# F103___2025-11-19.net
KiCad netlist of a schematic drawn in EasyEDA Pro
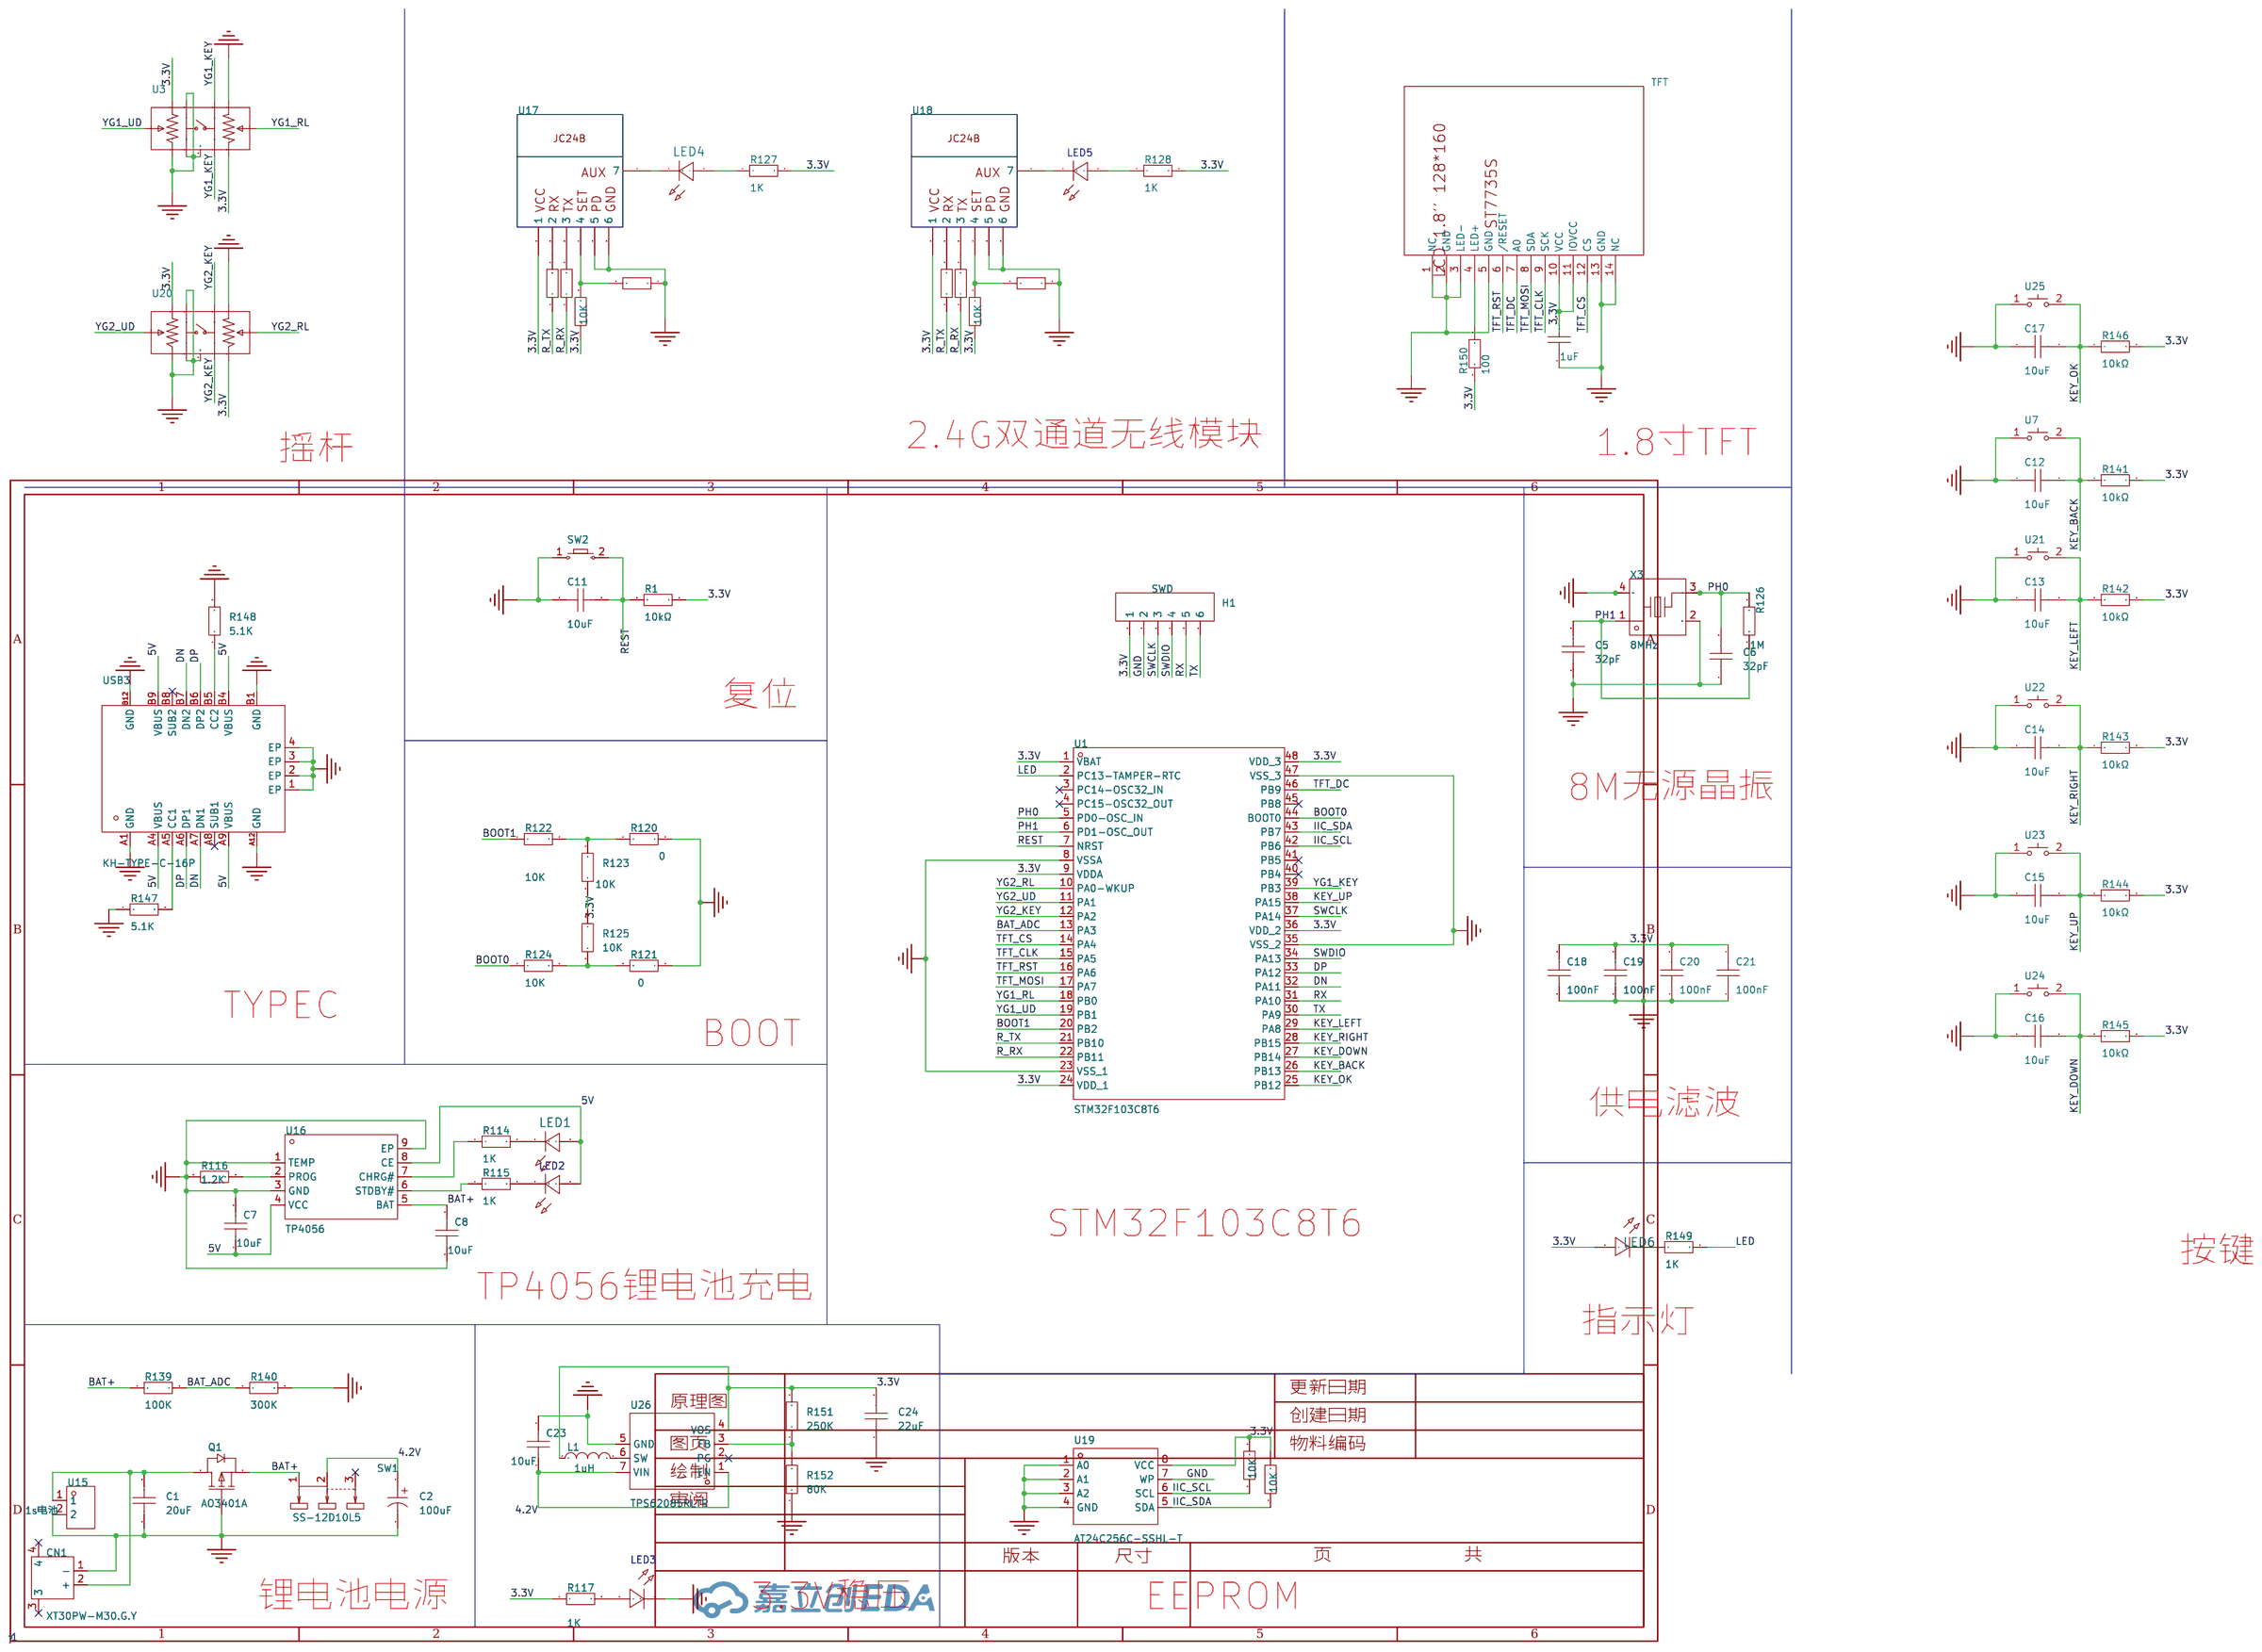
[diagram p0: schematic sheet]

(export (version "E")
  (design (tool "Eeschema 10.0.6"))
  (components
    (comp (ref "C1")
      (value "20uF")
      (footprint "easyedapro:C0805")
      (libsource (lib "easyedapro") (part "CapAcitance"))
    )
    (comp (ref "C2")
      (value "100uF")
      (footprint "easyedapro:CAP-SMD_BD6.3-L6.6-W6.6-LS7.4-FD")
      (description "容值:100uF;精度:±20%;额定电压:35V;纹波电流:87mA@120kHz;等效串联电阻:-;")
      (fields
        (field (name "Manufacturer Part") "RVT100UF35V67RV0034")
        (field (name "Manufacturer") "KNSCHA(科尼盛)")
      )
      (libsource (lib "easyedapro") (part "RVT100UF35V67RV0034"))
    )
    (comp (ref "C5")
      (value "32pF")
      (footprint "easyedapro:C0805")
      (libsource (lib "easyedapro") (part "CapAcitance"))
    )
    (comp (ref "C6")
      (value "32pF")
      (footprint "easyedapro:C0805")
      (libsource (lib "easyedapro") (part "CapAcitance"))
    )
    (comp (ref "C7")
      (value "10uF")
      (footprint "easyedapro:C0805")
      (libsource (lib "easyedapro") (part "CapAcitance"))
    )
    (comp (ref "C8")
      (value "10uF")
      (footprint "easyedapro:C0805")
      (libsource (lib "easyedapro") (part "CapAcitance"))
    )
    (comp (ref "C11")
      (value "10uF")
      (footprint "easyedapro:C0805")
      (libsource (lib "easyedapro") (part "CapAcitance"))
    )
    (comp (ref "C12")
      (value "10uF")
      (footprint "easyedapro:C0805")
      (libsource (lib "easyedapro") (part "CapAcitance"))
    )
    (comp (ref "C13")
      (value "10uF")
      (footprint "easyedapro:C0805")
      (libsource (lib "easyedapro") (part "CapAcitance"))
    )
    (comp (ref "C14")
      (value "10uF")
      (footprint "easyedapro:C0805")
      (libsource (lib "easyedapro") (part "CapAcitance"))
    )
    (comp (ref "C15")
      (value "10uF")
      (footprint "easyedapro:C0805")
      (libsource (lib "easyedapro") (part "CapAcitance"))
    )
    (comp (ref "C16")
      (value "10uF")
      (footprint "easyedapro:C0805")
      (libsource (lib "easyedapro") (part "CapAcitance"))
    )
    (comp (ref "C17")
      (value "10uF")
      (footprint "easyedapro:C0805")
      (libsource (lib "easyedapro") (part "CapAcitance"))
    )
    (comp (ref "C18")
      (value "100nF")
      (footprint "easyedapro:C0805")
      (libsource (lib "easyedapro") (part "CapAcitance"))
    )
    (comp (ref "C19")
      (value "100nF")
      (footprint "easyedapro:C0805")
      (libsource (lib "easyedapro") (part "CapAcitance"))
    )
    (comp (ref "C20")
      (value "100nF")
      (footprint "easyedapro:C0805")
      (libsource (lib "easyedapro") (part "CapAcitance"))
    )
    (comp (ref "C21")
      (value "100nF")
      (footprint "easyedapro:C0805")
      (libsource (lib "easyedapro") (part "CapAcitance"))
    )
    (comp (ref "C22")
      (value "1uF")
      (footprint "easyedapro:C0805")
      (libsource (lib "easyedapro") (part "CapAcitance"))
    )
    (comp (ref "C23")
      (value "10uF")
      (footprint "easyedapro:C0805")
      (libsource (lib "easyedapro") (part "CapAcitance"))
    )
    (comp (ref "C24")
      (value "22uF")
      (footprint "easyedapro:C0805")
      (libsource (lib "easyedapro") (part "CapAcitance"))
    )
    (comp (ref "CN1")
      (value "XT30PW-M30.G.Y")
      (footprint "easyedapro:CONN-TH_XT30PW-M")
      (description "类别:-;类型1:-;")
      (fields (field (name "Manufacturer") "AMASS(艾迈斯)"))
      (libsource (lib "easyedapro") (part "XT30PW-M"))
    )
    (comp (ref "H1")
      (value "SWD")
      (footprint "easyedapro:HDR-TH_6P-P2.54-V-M-1")
      (libsource (lib "easyedapro") (part "Header-Male-2.54_1x6"))
    )
    (comp (ref "L1")
      (value "1uH")
      (footprint "easyedapro:IND-SMD_L5.4-W5.2_FXL0530")
      (description "电感值:1uH;精度:±20%;额定电流:8.5A;饱和电流(Isat):11A;类型:一体成型电感;")
      (fields (field (name "Manufacturer Part") "FXL0530-1R0-M") (field (name "Manufacturer") "cjiang(长江微电)"))
      (libsource (lib "easyedapro") (part "FXL0530-1R0-M"))
    )
    (comp (ref "LCD2")
      (value "TFT")
      (footprint "easyedapro:1.8寸TFT")
      (description "1.8寸，ST7735S")
      (libsource (lib "easyedapro") (part "LCD-1.8&apos;&apos;-128*160-ST7735S"))
    )
    (comp (ref "LED1")
      (value "~")
      (footprint "easyedapro:LED_0805")
      (libsource (lib "easyedapro") (part "LED_R"))
    )
    (comp (ref "LED2")
      (value "~")
      (footprint "easyedapro:LED_0805")
      (libsource (lib "easyedapro") (part "LED_B"))
    )
    (comp (ref "LED3")
      (value "~")
      (footprint "easyedapro:LED_0805")
      (libsource (lib "easyedapro") (part "LED_G"))
    )
    (comp (ref "LED4")
      (value "~")
      (footprint "easyedapro:LED_0805")
      (libsource (lib "easyedapro") (part "LED_R"))
    )
    (comp (ref "LED5")
      (value "~")
      (footprint "easyedapro:LED_0805")
      (libsource (lib "easyedapro") (part "LED_B"))
    )
    (comp (ref "LED6")
      (value "~")
      (footprint "easyedapro:LED_0805")
      (libsource (lib "easyedapro") (part "LED_R"))
    )
    (comp (ref "Q1")
      (value "AO3401A")
      (footprint "easyedapro:SOT-23_L2.9-W1.3-P1.90-LS2.4-BR")
      (fields (field (name "Manufacturer") "AOS"))
      (libsource (lib "easyedapro") (part "AO3401A"))
    )
    (comp (ref "R1")
      (value "10kΩ")
      (footprint "easyedapro:R0805")
      (description "电阻类型:厚膜电阻;阻值:4.7kΩ;精度:±1%;功率:125mW;最大工作电压:150V;温度系数:±100ppm/°C;")
      (fields
        (field (name "Manufacturer Part") "0805W8F4701T5E")
        (field (name "Manufacturer") "UNI-ROYAL(厚声)")
      )
      (libsource (lib "easyedapro") (part "0805W8F4701T5E"))
    )
    (comp (ref "R114") (value "1K") (footprint "easyedapro:R0603") (libsource (lib "easyedapro") (part "电阻")))
    (comp (ref "R115") (value "1K") (footprint "easyedapro:R0603") (libsource (lib "easyedapro") (part "电阻")))
    (comp (ref "R116")
      (value "1.2K")
      (footprint "easyedapro:R0603")
      (libsource (lib "easyedapro") (part "电阻"))
    )
    (comp (ref "R117") (value "1K") (footprint "easyedapro:R0603") (libsource (lib "easyedapro") (part "电阻")))
    (comp (ref "R120") (value "0") (footprint "easyedapro:R0603") (libsource (lib "easyedapro") (part "电阻")))
    (comp (ref "R121") (value "0") (footprint "easyedapro:R0603") (libsource (lib "easyedapro") (part "电阻")))
    (comp (ref "R122")
      (value "10K")
      (footprint "easyedapro:R0603")
      (libsource (lib "easyedapro") (part "电阻"))
    )
    (comp (ref "R123")
      (value "10K")
      (footprint "easyedapro:R0603")
      (libsource (lib "easyedapro") (part "电阻"))
    )
    (comp (ref "R124")
      (value "10K")
      (footprint "easyedapro:R0603")
      (libsource (lib "easyedapro") (part "电阻"))
    )
    (comp (ref "R125")
      (value "10K")
      (footprint "easyedapro:R0603")
      (libsource (lib "easyedapro") (part "电阻"))
    )
    (comp (ref "R126") (value "1M") (footprint "easyedapro:R0603") (libsource (lib "easyedapro") (part "电阻")))
    (comp (ref "R127") (value "1K") (footprint "easyedapro:R0603") (libsource (lib "easyedapro") (part "电阻")))
    (comp (ref "R128") (value "1K") (footprint "easyedapro:R0603") (libsource (lib "easyedapro") (part "电阻")))
    (comp (ref "R129") (value "0") (footprint "easyedapro:R0603") (libsource (lib "easyedapro") (part "电阻")))
    (comp (ref "R130") (value "0") (footprint "easyedapro:R0603") (libsource (lib "easyedapro") (part "电阻")))
    (comp (ref "R131") (value "0") (footprint "easyedapro:R0603") (libsource (lib "easyedapro") (part "电阻")))
    (comp (ref "R132")
      (value "10K")
      (footprint "easyedapro:R0603")
      (libsource (lib "easyedapro") (part "电阻"))
    )
    (comp (ref "R133") (value "0") (footprint "easyedapro:R0603") (libsource (lib "easyedapro") (part "电阻")))
    (comp (ref "R134") (value "0") (footprint "easyedapro:R0603") (libsource (lib "easyedapro") (part "电阻")))
    (comp (ref "R135") (value "0") (footprint "easyedapro:R0603") (libsource (lib "easyedapro") (part "电阻")))
    (comp (ref "R136")
      (value "10K")
      (footprint "easyedapro:R0603")
      (libsource (lib "easyedapro") (part "电阻"))
    )
    (comp (ref "R137")
      (value "10K")
      (footprint "easyedapro:R0603")
      (libsource (lib "easyedapro") (part "电阻"))
    )
    (comp (ref "R138")
      (value "10K")
      (footprint "easyedapro:R0603")
      (libsource (lib "easyedapro") (part "电阻"))
    )
    (comp (ref "R139")
      (value "100K")
      (footprint "easyedapro:R0603")
      (libsource (lib "easyedapro") (part "电阻"))
    )
    (comp (ref "R140")
      (value "300K")
      (footprint "easyedapro:R0603")
      (libsource (lib "easyedapro") (part "电阻"))
    )
    (comp (ref "R141")
      (value "10kΩ")
      (footprint "easyedapro:R0805")
      (description "电阻类型:厚膜电阻;阻值:4.7kΩ;精度:±1%;功率:125mW;最大工作电压:150V;温度系数:±100ppm/°C;")
      (fields
        (field (name "Manufacturer Part") "0805W8F4701T5E")
        (field (name "Manufacturer") "UNI-ROYAL(厚声)")
      )
      (libsource (lib "easyedapro") (part "0805W8F4701T5E"))
    )
    (comp (ref "R142")
      (value "10kΩ")
      (footprint "easyedapro:R0805")
      (description "电阻类型:厚膜电阻;阻值:4.7kΩ;精度:±1%;功率:125mW;最大工作电压:150V;温度系数:±100ppm/°C;")
      (fields
        (field (name "Manufacturer Part") "0805W8F4701T5E")
        (field (name "Manufacturer") "UNI-ROYAL(厚声)")
      )
      (libsource (lib "easyedapro") (part "0805W8F4701T5E"))
    )
    (comp (ref "R143")
      (value "10kΩ")
      (footprint "easyedapro:R0805")
      (description "电阻类型:厚膜电阻;阻值:4.7kΩ;精度:±1%;功率:125mW;最大工作电压:150V;温度系数:±100ppm/°C;")
      (fields
        (field (name "Manufacturer Part") "0805W8F4701T5E")
        (field (name "Manufacturer") "UNI-ROYAL(厚声)")
      )
      (libsource (lib "easyedapro") (part "0805W8F4701T5E"))
    )
    (comp (ref "R144")
      (value "10kΩ")
      (footprint "easyedapro:R0805")
      (description "电阻类型:厚膜电阻;阻值:4.7kΩ;精度:±1%;功率:125mW;最大工作电压:150V;温度系数:±100ppm/°C;")
      (fields
        (field (name "Manufacturer Part") "0805W8F4701T5E")
        (field (name "Manufacturer") "UNI-ROYAL(厚声)")
      )
      (libsource (lib "easyedapro") (part "0805W8F4701T5E"))
    )
    (comp (ref "R145")
      (value "10kΩ")
      (footprint "easyedapro:R0805")
      (description "电阻类型:厚膜电阻;阻值:4.7kΩ;精度:±1%;功率:125mW;最大工作电压:150V;温度系数:±100ppm/°C;")
      (fields
        (field (name "Manufacturer Part") "0805W8F4701T5E")
        (field (name "Manufacturer") "UNI-ROYAL(厚声)")
      )
      (libsource (lib "easyedapro") (part "0805W8F4701T5E"))
    )
    (comp (ref "R146")
      (value "10kΩ")
      (footprint "easyedapro:R0805")
      (description "电阻类型:厚膜电阻;阻值:4.7kΩ;精度:±1%;功率:125mW;最大工作电压:150V;温度系数:±100ppm/°C;")
      (fields
        (field (name "Manufacturer Part") "0805W8F4701T5E")
        (field (name "Manufacturer") "UNI-ROYAL(厚声)")
      )
      (libsource (lib "easyedapro") (part "0805W8F4701T5E"))
    )
    (comp (ref "R147")
      (value "5.1K")
      (footprint "easyedapro:R0603")
      (libsource (lib "easyedapro") (part "电阻"))
    )
    (comp (ref "R148")
      (value "5.1K")
      (footprint "easyedapro:R0603")
      (libsource (lib "easyedapro") (part "电阻"))
    )
    (comp (ref "R149") (value "1K") (footprint "easyedapro:R0603") (libsource (lib "easyedapro") (part "电阻")))
    (comp (ref "R150")
      (value "100")
      (footprint "easyedapro:R0603")
      (libsource (lib "easyedapro") (part "电阻"))
    )
    (comp (ref "R151")
      (value "250K")
      (footprint "easyedapro:R0603")
      (libsource (lib "easyedapro") (part "电阻"))
    )
    (comp (ref "R152")
      (value "80K")
      (footprint "easyedapro:R0603")
      (libsource (lib "easyedapro") (part "电阻"))
    )
    (comp (ref "SW1")
      (value "SS-12D10L5")
      (footprint "easyedapro:SW-TH_SS-12D10L5")
      (description "电路结构:单刀双掷;安装方式:直插;开关颜色:黑色;额定电流(DC):3A;额定电压(DC):125V;额定电流(AC):3A;额定电压(AC):125V;机械寿命:1万次;")
      (fields (field (name "Manufacturer") "XKB Connectivity(中国星坤)"))
      (libsource (lib "easyedapro") (part "SS-12D10L5"))
    )
    (comp (ref "SW2")
      (value "~")
      (footprint "easyedapro:Key_SMD_3x4x2")
      (libsource (lib "easyedapro") (part "轻触按键x2"))
    )
    (comp (ref "U1")
      (value "STM32F103C8T6")
      (footprint "easyedapro:LQFP-48_L7.0-W7.0-P0.50-LS9.0-BL")
      (description "CPU内核:ARM-M3;CPU最大主频:72MHz;应用领域:-;")
      (fields (field (name "Manufacturer") "ST(意法半导体)"))
      (libsource (lib "easyedapro") (part "STM32F103C8T6"))
    )
    (comp (ref "U3")
      (value "YHE-YG13-013 SH3B166A5")
      (footprint "easyedapro:JOYTICK-TH_YHE-YG13-013-SH3B166A5")
      (description "霍尔电位器摇杆、摇杆电位器、操纵杆电位器，适用于航模玩具遥控器电位器、3D摇杆PS4手柄游戏机、无人机摇杆电位器、VR摇杆电位器、工业控制器")
      (fields (field (name "Manufacturer") "YTL(亚特联)"))
      (libsource (lib "easyedapro") (part "YHE-YG13-013 SH3B166A5"))
    )
    (comp (ref "U7")
      (value "TS-1199A26050")
      (footprint "easyedapro:SW-SMD_L6.0-W6.0-LS6.6")
      (fields (field (name "Manufacturer") "HanElectricity(瀚源)"))
      (libsource (lib "easyedapro") (part "TS-1199A26050"))
    )
    (comp (ref "U15")
      (value "1s电池")
      (footprint "easyedapro:CONN-TH_2P-P2.50_BX-XH2.54-2PZZ")
      (fields (field (name "Manufacturer Part") "BX-XH2.54-2PZZ") (field (name "Manufacturer") "Bossie(博锡)"))
      (libsource (lib "easyedapro") (part "BX-XH2.54-2PZZ"))
    )
    (comp (ref "U16")
      (value "TP4056")
      (footprint "easyedapro:ESOP-8_L4.9-W3.9-P1.27-LS6.0-BL-EP")
      (fields (field (name "Manufacturer") "UMW(友台半导体)"))
      (libsource (lib "easyedapro") (part "TP4056_C725790"))
    )
    (comp (ref "U17")
      (value "~")
      (footprint "easyedapro:JC24B")
      (description "J24B火蝠无线通信模块 距离200米  电压\n3.3V  USART串口")
      (libsource (lib "easyedapro") (part "JC24B"))
    )
    (comp (ref "U18")
      (value "~")
      (footprint "easyedapro:JC24B")
      (description "J24B火蝠无线通信模块 距离200米  电压\n3.3V  USART串口")
      (libsource (lib "easyedapro") (part "JC24B"))
    )
    (comp (ref "U19")
      (value "AT24C256C-SSHL-T")
      (footprint "easyedapro:SOIC-8_L4.9-W3.9-P1.27-LS6.0-BL")
      (description "存储器容量:256Kb (32K x 8);存储器接口类型:I2C;工作电压:1.7V ~ 5.5V;")
      (fields (field (name "Manufacturer") "MICROCHIP(美国微芯)"))
      (libsource (lib "easyedapro") (part "AT24C256C-SSHL-T"))
    )
    (comp (ref "U20")
      (value "YHE-YG13-013 SH3B166A5")
      (footprint "easyedapro:JOYTICK-TH_YHE-YG13-013-SH3B166A5")
      (description "霍尔电位器摇杆、摇杆电位器、操纵杆电位器，适用于航模玩具遥控器电位器、3D摇杆PS4手柄游戏机、无人机摇杆电位器、VR摇杆电位器、工业控制器")
      (fields (field (name "Manufacturer") "YTL(亚特联)"))
      (libsource (lib "easyedapro") (part "YHE-YG13-013 SH3B166A5"))
    )
    (comp (ref "U21")
      (value "TS-1199A26050")
      (footprint "easyedapro:SW-SMD_L6.0-W6.0-LS6.6")
      (fields (field (name "Manufacturer") "HanElectricity(瀚源)"))
      (libsource (lib "easyedapro") (part "TS-1199A26050"))
    )
    (comp (ref "U22")
      (value "TS-1199A26050")
      (footprint "easyedapro:SW-SMD_L6.0-W6.0-LS6.6")
      (fields (field (name "Manufacturer") "HanElectricity(瀚源)"))
      (libsource (lib "easyedapro") (part "TS-1199A26050"))
    )
    (comp (ref "U23")
      (value "TS-1199A26050")
      (footprint "easyedapro:SW-SMD_L6.0-W6.0-LS6.6")
      (fields (field (name "Manufacturer") "HanElectricity(瀚源)"))
      (libsource (lib "easyedapro") (part "TS-1199A26050"))
    )
    (comp (ref "U24")
      (value "TS-1199A26050")
      (footprint "easyedapro:SW-SMD_L6.0-W6.0-LS6.6")
      (fields (field (name "Manufacturer") "HanElectricity(瀚源)"))
      (libsource (lib "easyedapro") (part "TS-1199A26050"))
    )
    (comp (ref "U25")
      (value "TS-1199A26050")
      (footprint "easyedapro:SW-SMD_L6.0-W6.0-LS6.6")
      (fields (field (name "Manufacturer") "HanElectricity(瀚源)"))
      (libsource (lib "easyedapro") (part "TS-1199A26050"))
    )
    (comp (ref "U26")
      (value "TPS62085RLTR")
      (footprint "easyedapro:VSON-7_L2.0-W2.0-P0.5-TL")
      (description "功能类型:降压型;输出类型:可调;工作电压:2.5V~6V;输出电压:-;输出电流:3A;")
      (fields (field (name "Manufacturer") "TI(德州仪器)"))
      (libsource (lib "easyedapro") (part "TPS62085RLTR"))
    )
    (comp (ref "USB3")
      (value "KH-TYPE-C-16P")
      (footprint "easyedapro:USB-C-SMD_KH-TYPE-C-16P")
      (description "连接器类型:Type-C;标准:-;公母:母;端口数量:1;触点数量:16P;安装方式:卧贴;额定电流 - 电源:3A;工作温度范围:-40°C~+85°C;")
      (fields (field (name "Manufacturer") "kinghelm(金航标)"))
      (libsource (lib "easyedapro") (part "KH-TYPE-C-16P"))
    )
    (comp (ref "X3")
      (value "8MHz")
      (footprint "easyedapro:CRYSTAL-SMD_4P-L3.2-W2.5-BL")
      (description "晶振类型:贴片晶振;频率:8MHz;常温频差:±10ppm;外接负载电容:20pF;频率稳定度(全温):±20ppm;")
      (fields (field (name "Manufacturer Part") "X32258MSB4SI") (field (name "Manufacturer") "YXC(扬兴晶振)"))
      (libsource (lib "easyedapro") (part "X32258MSB4SI"))
    )
  )
  (nets
    (net (code "1") (name "/3.3V") (class "Default")
      (node (ref "C18") (pin "2") (pinfunction "2_2") (pintype "input"))
      (node (ref "C19") (pin "2") (pinfunction "2_2") (pintype "input"))
      (node (ref "C20") (pin "2") (pinfunction "2_2") (pintype "input"))
      (node (ref "C21") (pin "2") (pinfunction "2_2") (pintype "input"))
      (node (ref "C22") (pin "2") (pinfunction "2_2") (pintype "input"))
      (node (ref "C24") (pin "2") (pinfunction "2_2") (pintype "input"))
      (node (ref "H1") (pin "1") (pinfunction "1_1") (pintype "input"))
      (node (ref "L1") (pin "1") (pinfunction "1_1") (pintype "unspecified"))
      (node (ref "LCD2") (pin "10") (pinfunction "VCC_10") (pintype "unspecified"))
      (node (ref "LCD2") (pin "11") (pinfunction "IOVCC_11") (pintype "unspecified"))
      (node (ref "LED6") (pin "2") (pinfunction "A_2") (pintype "input"))
      (node (ref "R1") (pin "2") (pinfunction "2_2") (pintype "input"))
      (node (ref "R117") (pin "1") (pinfunction "1_1") (pintype "input"))
      (node (ref "R123") (pin "2") (pinfunction "2_2") (pintype "input"))
      (node (ref "R125") (pin "2") (pinfunction "2_2") (pintype "input"))
      (node (ref "R127") (pin "2") (pinfunction "2_2") (pintype "input"))
      (node (ref "R128") (pin "2") (pinfunction "2_2") (pintype "input"))
      (node (ref "R132") (pin "1") (pinfunction "1_1") (pintype "input"))
      (node (ref "R136") (pin "1") (pinfunction "1_1") (pintype "input"))
      (node (ref "R137") (pin "2") (pinfunction "2_2") (pintype "input"))
      (node (ref "R138") (pin "2") (pinfunction "2_2") (pintype "input"))
      (node (ref "R141") (pin "2") (pinfunction "2_2") (pintype "input"))
      (node (ref "R142") (pin "2") (pinfunction "2_2") (pintype "input"))
      (node (ref "R143") (pin "2") (pinfunction "2_2") (pintype "input"))
      (node (ref "R144") (pin "2") (pinfunction "2_2") (pintype "input"))
      (node (ref "R145") (pin "2") (pinfunction "2_2") (pintype "input"))
      (node (ref "R146") (pin "2") (pinfunction "2_2") (pintype "input"))
      (node (ref "R150") (pin "1") (pinfunction "1_1") (pintype "input"))
      (node (ref "R151") (pin "2") (pinfunction "2_2") (pintype "input"))
      (node (ref "U1") (pin "1") (pinfunction "VBAT_1") (pintype "unspecified"))
      (node (ref "U1") (pin "24") (pinfunction "VDD_1_24") (pintype "unspecified"))
      (node (ref "U1") (pin "36") (pinfunction "VDD_2_36") (pintype "unspecified"))
      (node (ref "U1") (pin "48") (pinfunction "VDD_3_48") (pintype "unspecified"))
      (node (ref "U1") (pin "9") (pinfunction "VDDA_9") (pintype "unspecified"))
      (node (ref "U17") (pin "1") (pinfunction "1_1") (pintype "input"))
      (node (ref "U18") (pin "1") (pinfunction "1_1") (pintype "input"))
      (node (ref "U19") (pin "8") (pinfunction "VCC_8") (pintype "input"))
      (node (ref "U20") (pin "3") (pinfunction "R1_3") (pintype "unspecified"))
      (node (ref "U20") (pin "6") (pinfunction "R2_6") (pintype "unspecified"))
      (node (ref "U26") (pin "4") (pinfunction "VOS_4") (pintype "unspecified"))
      (node (ref "U3") (pin "3") (pinfunction "R1_3") (pintype "unspecified"))
      (node (ref "U3") (pin "6") (pinfunction "R2_6") (pintype "unspecified"))
    )
    (net (code "2") (name "/4.2V") (class "Default")
      (node (ref "C2") (pin "1") (pinfunction "1_1") (pintype "input"))
      (node (ref "C23") (pin "1") (pinfunction "1_1") (pintype "input"))
      (node (ref "SW1") (pin "2") (pinfunction "2_2") (pintype "unspecified"))
      (node (ref "U26") (pin "1") (pinfunction "EN_1") (pintype "unspecified"))
      (node (ref "U26") (pin "7") (pinfunction "VIN_7") (pintype "unspecified"))
    )
    (net (code "3") (name "/5V") (class "Default")
      (node (ref "C7") (pin "1") (pinfunction "1_1") (pintype "input"))
      (node (ref "LED1") (pin "2") (pinfunction "A_2") (pintype "input"))
      (node (ref "LED2") (pin "2") (pinfunction "A_2") (pintype "input"))
      (node (ref "U16") (pin "4") (pinfunction "VCC_4") (pintype "unspecified"))
      (node (ref "U16") (pin "8") (pinfunction "CE_8") (pintype "unspecified"))
      (node (ref "USB3") (pin "A4") (pinfunction "VBUS_A4") (pintype "unspecified"))
      (node (ref "USB3") (pin "A9") (pinfunction "VBUS_A9") (pintype "unspecified"))
      (node (ref "USB3") (pin "B4") (pinfunction "VBUS_B4") (pintype "unspecified"))
      (node (ref "USB3") (pin "B9") (pinfunction "VBUS_B9") (pintype "unspecified"))
    )
    (net (code "4") (name "/BAT+") (class "Default")
      (node (ref "C8") (pin "2") (pinfunction "2_2") (pintype "input"))
      (node (ref "Q1") (pin "2") (pinfunction "S_2") (pintype "unspecified"))
      (node (ref "R139") (pin "1") (pinfunction "1_1") (pintype "input"))
      (node (ref "SW1") (pin "1") (pinfunction "1_1") (pintype "unspecified"))
      (node (ref "U16") (pin "5") (pinfunction "BAT_5") (pintype "unspecified"))
    )
    (net (code "5") (name "/BAT_ADC") (class "Default")
      (node (ref "R139") (pin "2") (pinfunction "2_2") (pintype "input"))
      (node (ref "R140") (pin "1") (pinfunction "1_1") (pintype "input"))
      (node (ref "U1") (pin "13") (pinfunction "PA3_13") (pintype "unspecified"))
    )
    (net (code "6") (name "/BOOT0") (class "Default")
      (node (ref "R124") (pin "1") (pinfunction "1_1") (pintype "input"))
      (node (ref "U1") (pin "44") (pinfunction "BOOT0_44") (pintype "unspecified"))
    )
    (net (code "7") (name "/BOOT1") (class "Default")
      (node (ref "R122") (pin "1") (pinfunction "1_1") (pintype "input"))
      (node (ref "U1") (pin "20") (pinfunction "PB2_20") (pintype "unspecified"))
    )
    (net (code "8") (name "/DN") (class "Default")
      (node (ref "U1") (pin "32") (pinfunction "PA11_32") (pintype "unspecified"))
      (node (ref "USB3") (pin "A7") (pinfunction "DN1_A7") (pintype "unspecified"))
      (node (ref "USB3") (pin "B7") (pinfunction "DN2_B7") (pintype "unspecified"))
    )
    (net (code "9") (name "/DP") (class "Default")
      (node (ref "U1") (pin "33") (pinfunction "PA12_33") (pintype "unspecified"))
      (node (ref "USB3") (pin "A6") (pinfunction "DP1_A6") (pintype "unspecified"))
      (node (ref "USB3") (pin "B6") (pinfunction "DP2_B6") (pintype "unspecified"))
    )
    (net (code "10") (name "/IIC_SCL") (class "Default")
      (node (ref "R137") (pin "1") (pinfunction "1_1") (pintype "input"))
      (node (ref "U1") (pin "42") (pinfunction "PB6_42") (pintype "unspecified"))
      (node (ref "U19") (pin "6") (pinfunction "SCL_6") (pintype "input"))
    )
    (net (code "11") (name "/IIC_SDA") (class "Default")
      (node (ref "R138") (pin "1") (pinfunction "1_1") (pintype "input"))
      (node (ref "U1") (pin "43") (pinfunction "PB7_43") (pintype "unspecified"))
      (node (ref "U19") (pin "5") (pinfunction "SDA_5") (pintype "input"))
    )
    (net (code "12") (name "/KEY_BACK") (class "Default")
      (node (ref "C12") (pin "2") (pinfunction "2_2") (pintype "input"))
      (node (ref "R141") (pin "1") (pinfunction "1_1") (pintype "input"))
      (node (ref "U1") (pin "26") (pinfunction "PB13_26") (pintype "unspecified"))
      (node (ref "U7") (pin "2") (pinfunction "2_2") (pintype "unspecified"))
    )
    (net (code "13") (name "/KEY_DOWN") (class "Default")
      (node (ref "C16") (pin "2") (pinfunction "2_2") (pintype "input"))
      (node (ref "R145") (pin "1") (pinfunction "1_1") (pintype "input"))
      (node (ref "U1") (pin "27") (pinfunction "PB14_27") (pintype "unspecified"))
      (node (ref "U24") (pin "2") (pinfunction "2_2") (pintype "unspecified"))
    )
    (net (code "14") (name "/KEY_LEFT") (class "Default")
      (node (ref "C13") (pin "2") (pinfunction "2_2") (pintype "input"))
      (node (ref "R142") (pin "1") (pinfunction "1_1") (pintype "input"))
      (node (ref "U1") (pin "29") (pinfunction "PA8_29") (pintype "unspecified"))
      (node (ref "U21") (pin "2") (pinfunction "2_2") (pintype "unspecified"))
    )
    (net (code "15") (name "/KEY_OK") (class "Default")
      (node (ref "C17") (pin "2") (pinfunction "2_2") (pintype "input"))
      (node (ref "R146") (pin "1") (pinfunction "1_1") (pintype "input"))
      (node (ref "U1") (pin "25") (pinfunction "PB12_25") (pintype "unspecified"))
      (node (ref "U25") (pin "2") (pinfunction "2_2") (pintype "unspecified"))
    )
    (net (code "16") (name "/KEY_RIGHT") (class "Default")
      (node (ref "C14") (pin "2") (pinfunction "2_2") (pintype "input"))
      (node (ref "R143") (pin "1") (pinfunction "1_1") (pintype "input"))
      (node (ref "U1") (pin "28") (pinfunction "PB15_28") (pintype "unspecified"))
      (node (ref "U22") (pin "2") (pinfunction "2_2") (pintype "unspecified"))
    )
    (net (code "17") (name "/KEY_UP") (class "Default")
      (node (ref "C15") (pin "2") (pinfunction "2_2") (pintype "input"))
      (node (ref "R144") (pin "1") (pinfunction "1_1") (pintype "input"))
      (node (ref "U1") (pin "38") (pinfunction "PA15_38") (pintype "unspecified"))
      (node (ref "U23") (pin "2") (pinfunction "2_2") (pintype "unspecified"))
    )
    (net (code "18") (name "/LED") (class "Default")
      (node (ref "R149") (pin "2") (pinfunction "2_2") (pintype "input"))
      (node (ref "U1") (pin "2") (pinfunction "PC13-TAMPER-RTC_2") (pintype "unspecified"))
    )
    (net (code "19") (name "/PH0") (class "Default")
      (node (ref "C6") (pin "2") (pinfunction "2_2") (pintype "input"))
      (node (ref "R126") (pin "1") (pinfunction "1_1") (pintype "input"))
      (node (ref "U1") (pin "5") (pinfunction "PD0-OSC_IN_5") (pintype "unspecified"))
      (node (ref "X3") (pin "3") (pinfunction "3_3") (pintype "input"))
    )
    (net (code "20") (name "/PH1") (class "Default")
      (node (ref "C5") (pin "2") (pinfunction "2_2") (pintype "input"))
      (node (ref "R126") (pin "2") (pinfunction "2_2") (pintype "input"))
      (node (ref "U1") (pin "6") (pinfunction "PD1-OSC_OUT_6") (pintype "unspecified"))
      (node (ref "X3") (pin "1") (pinfunction "1_1") (pintype "input"))
    )
    (net (code "21") (name "/REST") (class "Default")
      (node (ref "C11") (pin "2") (pinfunction "2_2") (pintype "input"))
      (node (ref "R1") (pin "1") (pinfunction "1_1") (pintype "input"))
      (node (ref "SW2") (pin "2") (pinfunction "2_2") (pintype "input"))
      (node (ref "U1") (pin "7") (pinfunction "NRST_7") (pintype "unspecified"))
    )
    (net (code "22") (name "/RX") (class "Default")
      (node (ref "H1") (pin "5") (pinfunction "5_5") (pintype "input"))
      (node (ref "U1") (pin "31") (pinfunction "PA10_31") (pintype "unspecified"))
    )
    (net (code "23") (name "/R_RX") (class "Default")
      (node (ref "R130") (pin "1") (pinfunction "1_1") (pintype "input"))
      (node (ref "R134") (pin "1") (pinfunction "1_1") (pintype "input"))
      (node (ref "U1") (pin "22") (pinfunction "PB11_22") (pintype "unspecified"))
    )
    (net (code "24") (name "/R_TX") (class "Default")
      (node (ref "R129") (pin "1") (pinfunction "1_1") (pintype "input"))
      (node (ref "R133") (pin "1") (pinfunction "1_1") (pintype "input"))
      (node (ref "U1") (pin "21") (pinfunction "PB10_21") (pintype "unspecified"))
    )
    (net (code "25") (name "/SWCLK") (class "Default")
      (node (ref "H1") (pin "3") (pinfunction "3_3") (pintype "input"))
      (node (ref "U1") (pin "37") (pinfunction "PA14_37") (pintype "unspecified"))
    )
    (net (code "26") (name "/SWDIO") (class "Default")
      (node (ref "H1") (pin "4") (pinfunction "4_4") (pintype "input"))
      (node (ref "U1") (pin "34") (pinfunction "PA13_34") (pintype "unspecified"))
    )
    (net (code "27") (name "/TFT_CLK") (class "Default")
      (node (ref "LCD2") (pin "9") (pinfunction "SCK_9") (pintype "unspecified"))
      (node (ref "U1") (pin "15") (pinfunction "PA5_15") (pintype "unspecified"))
    )
    (net (code "28") (name "/TFT_CS") (class "Default")
      (node (ref "LCD2") (pin "12") (pinfunction "CS_12") (pintype "unspecified"))
      (node (ref "U1") (pin "14") (pinfunction "PA4_14") (pintype "unspecified"))
    )
    (net (code "29") (name "/TFT_DC") (class "Default")
      (node (ref "LCD2") (pin "7") (pinfunction "A0_7") (pintype "unspecified"))
      (node (ref "U1") (pin "46") (pinfunction "PB9_46") (pintype "unspecified"))
    )
    (net (code "30") (name "/TFT_MOSI") (class "Default")
      (node (ref "LCD2") (pin "8") (pinfunction "SDA_8") (pintype "unspecified"))
      (node (ref "U1") (pin "17") (pinfunction "PA7_17") (pintype "unspecified"))
    )
    (net (code "31") (name "/TFT_RST") (class "Default")
      (node (ref "LCD2") (pin "6") (pinfunction "/RESET_6") (pintype "unspecified"))
      (node (ref "U1") (pin "16") (pinfunction "PA6_16") (pintype "unspecified"))
    )
    (net (code "32") (name "/TX") (class "Default")
      (node (ref "H1") (pin "6") (pinfunction "6_6") (pintype "input"))
      (node (ref "U1") (pin "30") (pinfunction "PA9_30") (pintype "unspecified"))
    )
    (net (code "33") (name "/YG1_KEY") (class "Default")
      (node (ref "U1") (pin "39") (pinfunction "PB3_39") (pintype "unspecified"))
      (node (ref "U3") (pin "7") (pinfunction "S1_7") (pintype "unspecified"))
      (node (ref "U3") (pin "8") (pinfunction "S2_8") (pintype "unspecified"))
    )
    (net (code "34") (name "/YG1_RL") (class "Default")
      (node (ref "U1") (pin "18") (pinfunction "PB0_18") (pintype "unspecified"))
      (node (ref "U3") (pin "5") (pinfunction "R2_5") (pintype "unspecified"))
    )
    (net (code "35") (name "/YG1_UD") (class "Default")
      (node (ref "U1") (pin "19") (pinfunction "PB1_19") (pintype "unspecified"))
      (node (ref "U3") (pin "2") (pinfunction "R1_2") (pintype "unspecified"))
    )
    (net (code "36") (name "/YG2_KEY") (class "Default")
      (node (ref "U1") (pin "12") (pinfunction "PA2_12") (pintype "unspecified"))
      (node (ref "U20") (pin "7") (pinfunction "S1_7") (pintype "unspecified"))
      (node (ref "U20") (pin "8") (pinfunction "S2_8") (pintype "unspecified"))
    )
    (net (code "37") (name "/YG2_RL") (class "Default")
      (node (ref "U1") (pin "10") (pinfunction "PA0-WKUP_10") (pintype "unspecified"))
      (node (ref "U20") (pin "5") (pinfunction "R2_5") (pintype "unspecified"))
    )
    (net (code "38") (name "/YG2_UD") (class "Default")
      (node (ref "U1") (pin "11") (pinfunction "PA1_11") (pintype "unspecified"))
      (node (ref "U20") (pin "2") (pinfunction "R1_2") (pintype "unspecified"))
    )
    (net (code "39") (name "GND") (class "Default")
      (node (ref "C1") (pin "1") (pinfunction "1_1") (pintype "input"))
      (node (ref "C11") (pin "1") (pinfunction "1_1") (pintype "input"))
      (node (ref "C12") (pin "1") (pinfunction "1_1") (pintype "input"))
      (node (ref "C13") (pin "1") (pinfunction "1_1") (pintype "input"))
      (node (ref "C14") (pin "1") (pinfunction "1_1") (pintype "input"))
      (node (ref "C15") (pin "1") (pinfunction "1_1") (pintype "input"))
      (node (ref "C16") (pin "1") (pinfunction "1_1") (pintype "input"))
      (node (ref "C17") (pin "1") (pinfunction "1_1") (pintype "input"))
      (node (ref "C18") (pin "1") (pinfunction "1_1") (pintype "input"))
      (node (ref "C19") (pin "1") (pinfunction "1_1") (pintype "input"))
      (node (ref "C2") (pin "2") (pinfunction "2_2") (pintype "input"))
      (node (ref "C20") (pin "1") (pinfunction "1_1") (pintype "input"))
      (node (ref "C21") (pin "1") (pinfunction "1_1") (pintype "input"))
      (node (ref "C22") (pin "1") (pinfunction "1_1") (pintype "input"))
      (node (ref "C23") (pin "2") (pinfunction "2_2") (pintype "input"))
      (node (ref "C24") (pin "1") (pinfunction "1_1") (pintype "input"))
      (node (ref "C5") (pin "1") (pinfunction "1_1") (pintype "input"))
      (node (ref "C6") (pin "1") (pinfunction "1_1") (pintype "input"))
      (node (ref "C7") (pin "2") (pinfunction "2_2") (pintype "input"))
      (node (ref "C8") (pin "1") (pinfunction "1_1") (pintype "input"))
      (node (ref "CN1") (pin "1") (pinfunction "-_1") (pintype "unspecified"))
      (node (ref "H1") (pin "2") (pinfunction "2_2") (pintype "input"))
      (node (ref "LCD2") (pin "1") (pinfunction "NC_1") (pintype "unspecified"))
      (node (ref "LCD2") (pin "13") (pinfunction "GND_13") (pintype "unspecified"))
      (node (ref "LCD2") (pin "14") (pinfunction "NC_14") (pintype "unspecified"))
      (node (ref "LCD2") (pin "2") (pinfunction "GND_2") (pintype "unspecified"))
      (node (ref "LCD2") (pin "3") (pinfunction "LED-_3") (pintype "unspecified"))
      (node (ref "LCD2") (pin "5") (pinfunction "GND_5") (pintype "unspecified"))
      (node (ref "LED3") (pin "1") (pinfunction "C_1") (pintype "input"))
      (node (ref "Q1") (pin "1") (pinfunction "G_1") (pintype "unspecified"))
      (node (ref "R116") (pin "1") (pinfunction "1_1") (pintype "input"))
      (node (ref "R120") (pin "2") (pinfunction "2_2") (pintype "input"))
      (node (ref "R121") (pin "1") (pinfunction "1_1") (pintype "input"))
      (node (ref "R131") (pin "1") (pinfunction "1_1") (pintype "input"))
      (node (ref "R135") (pin "1") (pinfunction "1_1") (pintype "input"))
      (node (ref "R140") (pin "2") (pinfunction "2_2") (pintype "input"))
      (node (ref "R147") (pin "1") (pinfunction "1_1") (pintype "input"))
      (node (ref "R148") (pin "2") (pinfunction "2_2") (pintype "input"))
      (node (ref "R152") (pin "1") (pinfunction "1_1") (pintype "input"))
      (node (ref "SW2") (pin "1") (pinfunction "1_1") (pintype "input"))
      (node (ref "U1") (pin "23") (pinfunction "VSS_1_23") (pintype "unspecified"))
      (node (ref "U1") (pin "35") (pinfunction "VSS_2_35") (pintype "unspecified"))
      (node (ref "U1") (pin "47") (pinfunction "VSS_3_47") (pintype "unspecified"))
      (node (ref "U1") (pin "8") (pinfunction "VSSA_8") (pintype "unspecified"))
      (node (ref "U15") (pin "2") (pinfunction "2_2") (pintype "unspecified"))
      (node (ref "U16") (pin "1") (pinfunction "TEMP_1") (pintype "unspecified"))
      (node (ref "U16") (pin "3") (pinfunction "GND_3") (pintype "unspecified"))
      (node (ref "U16") (pin "9") (pinfunction "EP_9") (pintype "unspecified"))
      (node (ref "U17") (pin "5") (pinfunction "5_5") (pintype "input"))
      (node (ref "U17") (pin "6") (pinfunction "6_6") (pintype "input"))
      (node (ref "U18") (pin "5") (pinfunction "5_5") (pintype "input"))
      (node (ref "U18") (pin "6") (pinfunction "6_6") (pintype "input"))
      (node (ref "U19") (pin "1") (pinfunction "A0_1") (pintype "input"))
      (node (ref "U19") (pin "2") (pinfunction "A1_2") (pintype "input"))
      (node (ref "U19") (pin "3") (pinfunction "A2_3") (pintype "input"))
      (node (ref "U19") (pin "4") (pinfunction "GND_4") (pintype "input"))
      (node (ref "U19") (pin "7") (pinfunction "WP_7") (pintype "input"))
      (node (ref "U20") (pin "1") (pinfunction "R1_1") (pintype "unspecified"))
      (node (ref "U20") (pin "10") (pinfunction "S4_10") (pintype "unspecified"))
      (node (ref "U20") (pin "11") (pinfunction "SHELL_11") (pintype "unspecified"))
      (node (ref "U20") (pin "4") (pinfunction "R2_4") (pintype "unspecified"))
      (node (ref "U20") (pin "9") (pinfunction "S3_9") (pintype "unspecified"))
      (node (ref "U21") (pin "1") (pinfunction "1_1") (pintype "unspecified"))
      (node (ref "U22") (pin "1") (pinfunction "1_1") (pintype "unspecified"))
      (node (ref "U23") (pin "1") (pinfunction "1_1") (pintype "unspecified"))
      (node (ref "U24") (pin "1") (pinfunction "1_1") (pintype "unspecified"))
      (node (ref "U25") (pin "1") (pinfunction "1_1") (pintype "unspecified"))
      (node (ref "U26") (pin "5") (pinfunction "GND_5") (pintype "unspecified"))
      (node (ref "U3") (pin "1") (pinfunction "R1_1") (pintype "unspecified"))
      (node (ref "U3") (pin "10") (pinfunction "S4_10") (pintype "unspecified"))
      (node (ref "U3") (pin "11") (pinfunction "SHELL_11") (pintype "unspecified"))
      (node (ref "U3") (pin "4") (pinfunction "R2_4") (pintype "unspecified"))
      (node (ref "U3") (pin "9") (pinfunction "S3_9") (pintype "unspecified"))
      (node (ref "U7") (pin "1") (pinfunction "1_1") (pintype "unspecified"))
      (node (ref "USB3") (pin "1") (pinfunction "EP_1") (pintype "unspecified"))
      (node (ref "USB3") (pin "2") (pinfunction "EP_2") (pintype "unspecified"))
      (node (ref "USB3") (pin "3") (pinfunction "EP_3") (pintype "unspecified"))
      (node (ref "USB3") (pin "4") (pinfunction "EP_4") (pintype "unspecified"))
      (node (ref "USB3") (pin "A1") (pinfunction "GND_A1") (pintype "unspecified"))
      (node (ref "USB3") (pin "A12") (pinfunction "GND_A12") (pintype "unspecified"))
      (node (ref "USB3") (pin "B1") (pinfunction "GND_B1") (pintype "unspecified"))
      (node (ref "USB3") (pin "B12") (pinfunction "GND_B12") (pintype "unspecified"))
      (node (ref "X3") (pin "2") (pinfunction "GND_2") (pintype "input"))
      (node (ref "X3") (pin "4") (pinfunction "GND_4") (pintype "input"))
    )
    (net (code "40") (name "Net-(CN1-+)") (class "Default")
      (node (ref "C1") (pin "2") (pinfunction "2_2") (pintype "input"))
      (node (ref "CN1") (pin "2") (pinfunction "+_2") (pintype "unspecified"))
      (node (ref "Q1") (pin "3") (pinfunction "D_3") (pintype "unspecified"))
      (node (ref "U15") (pin "1") (pinfunction "1_1") (pintype "unspecified"))
    )
    (net (code "41") (name "Net-(LCD2-LED+)") (class "Default")
      (node (ref "LCD2") (pin "4") (pinfunction "LED+_4") (pintype "unspecified"))
      (node (ref "R150") (pin "2") (pinfunction "2_2") (pintype "input"))
    )
    (net (code "42") (name "Net-(LED1-C)") (class "Default")
      (node (ref "LED1") (pin "1") (pinfunction "C_1") (pintype "input"))
      (node (ref "R114") (pin "2") (pinfunction "2_2") (pintype "input"))
    )
    (net (code "43") (name "Net-(LED2-C)") (class "Default")
      (node (ref "LED2") (pin "1") (pinfunction "C_1") (pintype "input"))
      (node (ref "R115") (pin "2") (pinfunction "2_2") (pintype "input"))
    )
    (net (code "44") (name "Net-(LED3-A)") (class "Default")
      (node (ref "LED3") (pin "2") (pinfunction "A_2") (pintype "input"))
      (node (ref "R117") (pin "2") (pinfunction "2_2") (pintype "input"))
    )
    (net (code "45") (name "Net-(LED4-A)") (class "Default")
      (node (ref "LED4") (pin "2") (pinfunction "A_2") (pintype "input"))
      (node (ref "R127") (pin "1") (pinfunction "1_1") (pintype "input"))
    )
    (net (code "46") (name "Net-(LED4-C)") (class "Default")
      (node (ref "LED4") (pin "1") (pinfunction "C_1") (pintype "input"))
      (node (ref "U17") (pin "7") (pinfunction "7_7") (pintype "input"))
    )
    (net (code "47") (name "Net-(LED5-A)") (class "Default")
      (node (ref "LED5") (pin "2") (pinfunction "A_2") (pintype "input"))
      (node (ref "R128") (pin "1") (pinfunction "1_1") (pintype "input"))
    )
    (net (code "48") (name "Net-(LED5-C)") (class "Default")
      (node (ref "LED5") (pin "1") (pinfunction "C_1") (pintype "input"))
      (node (ref "U18") (pin "7") (pinfunction "7_7") (pintype "input"))
    )
    (net (code "49") (name "Net-(LED6-C)") (class "Default")
      (node (ref "LED6") (pin "1") (pinfunction "C_1") (pintype "input"))
      (node (ref "R149") (pin "1") (pinfunction "1_1") (pintype "input"))
    )
    (net (code "50") (name "Net-(R120-Pad1)") (class "Default")
      (node (ref "R120") (pin "1") (pinfunction "1_1") (pintype "input"))
      (node (ref "R122") (pin "2") (pinfunction "2_2") (pintype "input"))
      (node (ref "R123") (pin "1") (pinfunction "1_1") (pintype "input"))
    )
    (net (code "51") (name "Net-(R121-Pad2)") (class "Default")
      (node (ref "R121") (pin "2") (pinfunction "2_2") (pintype "input"))
      (node (ref "R124") (pin "2") (pinfunction "2_2") (pintype "input"))
      (node (ref "R125") (pin "1") (pinfunction "1_1") (pintype "input"))
    )
    (net (code "52") (name "Net-(R129-Pad2)") (class "Default")
      (node (ref "R129") (pin "2") (pinfunction "2_2") (pintype "input"))
      (node (ref "U17") (pin "2") (pinfunction "2_2") (pintype "input"))
    )
    (net (code "53") (name "Net-(R130-Pad2)") (class "Default")
      (node (ref "R130") (pin "2") (pinfunction "2_2") (pintype "input"))
      (node (ref "U17") (pin "3") (pinfunction "3_3") (pintype "input"))
    )
    (net (code "54") (name "Net-(R131-Pad2)") (class "Default")
      (node (ref "R131") (pin "2") (pinfunction "2_2") (pintype "input"))
      (node (ref "R132") (pin "2") (pinfunction "2_2") (pintype "input"))
      (node (ref "U17") (pin "4") (pinfunction "4_4") (pintype "input"))
    )
    (net (code "55") (name "Net-(R133-Pad2)") (class "Default")
      (node (ref "R133") (pin "2") (pinfunction "2_2") (pintype "input"))
      (node (ref "U18") (pin "2") (pinfunction "2_2") (pintype "input"))
    )
    (net (code "56") (name "Net-(R134-Pad2)") (class "Default")
      (node (ref "R134") (pin "2") (pinfunction "2_2") (pintype "input"))
      (node (ref "U18") (pin "3") (pinfunction "3_3") (pintype "input"))
    )
    (net (code "57") (name "Net-(R135-Pad2)") (class "Default")
      (node (ref "R135") (pin "2") (pinfunction "2_2") (pintype "input"))
      (node (ref "R136") (pin "2") (pinfunction "2_2") (pintype "input"))
      (node (ref "U18") (pin "4") (pinfunction "4_4") (pintype "input"))
    )
    (net (code "58") (name "Net-(U16-CHRG#)") (class "Default")
      (node (ref "R114") (pin "1") (pinfunction "1_1") (pintype "input"))
      (node (ref "U16") (pin "7") (pinfunction "CHRG#_7") (pintype "unspecified"))
    )
    (net (code "59") (name "Net-(U16-PROG)") (class "Default")
      (node (ref "R116") (pin "2") (pinfunction "2_2") (pintype "input"))
      (node (ref "U16") (pin "2") (pinfunction "PROG_2") (pintype "unspecified"))
    )
    (net (code "60") (name "Net-(U16-STDBY#)") (class "Default")
      (node (ref "R115") (pin "1") (pinfunction "1_1") (pintype "input"))
      (node (ref "U16") (pin "6") (pinfunction "STDBY#_6") (pintype "unspecified"))
    )
    (net (code "61") (name "Net-(U26-FB)") (class "Default")
      (node (ref "R151") (pin "1") (pinfunction "1_1") (pintype "input"))
      (node (ref "R152") (pin "2") (pinfunction "2_2") (pintype "input"))
      (node (ref "U26") (pin "3") (pinfunction "FB_3") (pintype "unspecified"))
    )
    (net (code "62") (name "Net-(U26-SW)") (class "Default")
      (node (ref "L1") (pin "2") (pinfunction "2_2") (pintype "unspecified"))
      (node (ref "U26") (pin "6") (pinfunction "SW_6") (pintype "unspecified"))
    )
    (net (code "63") (name "Net-(USB3-CC1)") (class "Default")
      (node (ref "R147") (pin "2") (pinfunction "2_2") (pintype "input"))
      (node (ref "USB3") (pin "A5") (pinfunction "CC1_A5") (pintype "unspecified"))
    )
    (net (code "64") (name "Net-(USB3-CC2)") (class "Default")
      (node (ref "R148") (pin "1") (pinfunction "1_1") (pintype "input"))
      (node (ref "USB3") (pin "B5") (pinfunction "CC2_B5") (pintype "unspecified"))
    )
    (net (code "65") (name "unconnected-(CN1-Pad3)") (class "Default")
      (node (ref "CN1") (pin "3") (pinfunction "3_3") (pintype "unspecified+no_connect"))
    )
    (net (code "66") (name "unconnected-(CN1-Pad4)") (class "Default")
      (node (ref "CN1") (pin "4") (pinfunction "4_4") (pintype "unspecified+no_connect"))
    )
    (net (code "67") (name "unconnected-(SW1-Pad3)") (class "Default")
      (node (ref "SW1") (pin "3") (pinfunction "3_3") (pintype "unspecified+no_connect"))
    )
    (net (code "68") (name "unconnected-(U1-PB4-Pad40)") (class "Default")
      (node (ref "U1") (pin "40") (pinfunction "PB4_40") (pintype "unspecified+no_connect"))
    )
    (net (code "69") (name "unconnected-(U1-PB5-Pad41)") (class "Default")
      (node (ref "U1") (pin "41") (pinfunction "PB5_41") (pintype "unspecified+no_connect"))
    )
    (net (code "70") (name "unconnected-(U1-PB8-Pad45)") (class "Default")
      (node (ref "U1") (pin "45") (pinfunction "PB8_45") (pintype "unspecified+no_connect"))
    )
    (net (code "71") (name "unconnected-(U1-PC14-OSC32_IN-Pad3)") (class "Default")
      (node (ref "U1") (pin "3") (pinfunction "PC14-OSC32_IN_3") (pintype "unspecified+no_connect"))
    )
    (net (code "72") (name "unconnected-(U1-PC15-OSC32_OUT-Pad4)") (class "Default")
      (node (ref "U1") (pin "4") (pinfunction "PC15-OSC32_OUT_4") (pintype "unspecified+no_connect"))
    )
    (net (code "73") (name "unconnected-(U26-PG-Pad2)") (class "Default")
      (node (ref "U26") (pin "2") (pinfunction "PG_2") (pintype "unspecified+no_connect"))
    )
    (net (code "74") (name "unconnected-(USB3-SUB1-PadA8)") (class "Default")
      (node (ref "USB3") (pin "A8") (pinfunction "SUB1_A8") (pintype "unspecified+no_connect"))
    )
    (net (code "75") (name "unconnected-(USB3-SUB2-PadB8)") (class "Default")
      (node (ref "USB3") (pin "B8") (pinfunction "SUB2_B8") (pintype "unspecified+no_connect"))
    )
  )
)
